# MCU.net
KiCad netlist of a schematic drawn in Altium Designer
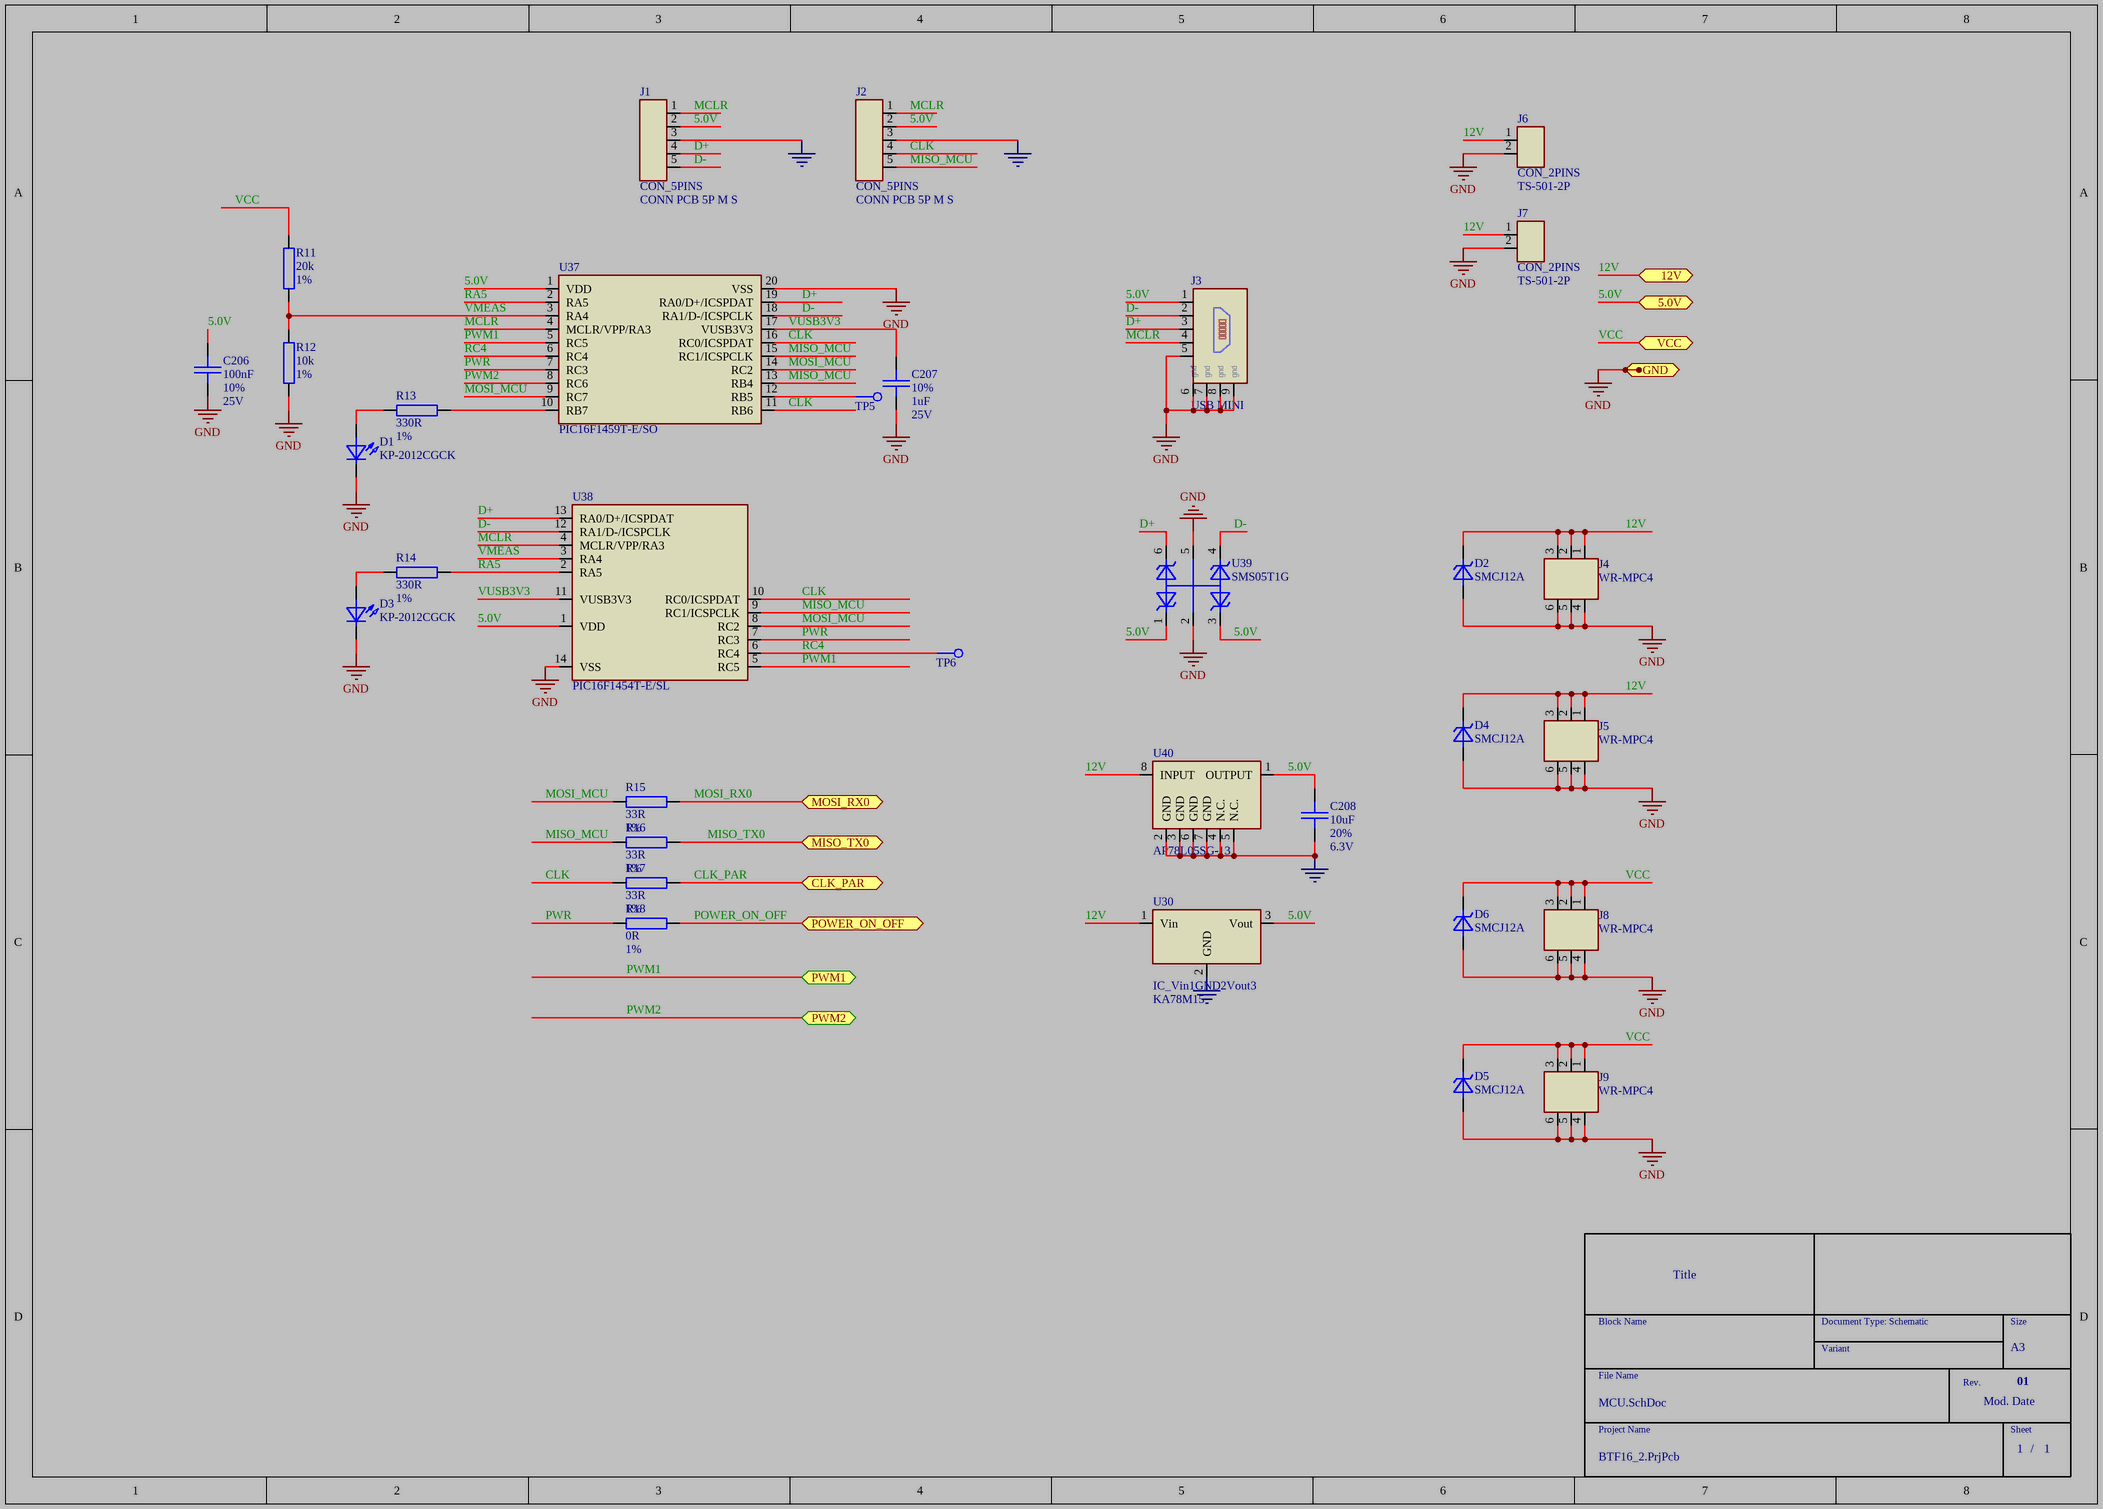
[diagram p0: MCU.SchDoc]

(export (version "E")
  (design (tool "Eeschema 10.0.6"))
  (components
    (comp (ref "C206")
      (value "C")
      (footprint "SMD_0402_CAPC1005X55N")
      (fields
        (field (name "DB_PART_NUMBER") "CAP000047469")
        (field (name "DB_VALUE") "100nF")
        (field (name "DB_TOLERANCE") "10%")
        (field (name "DB_VOLTAGE") "25V")
        (field (name "DB_MANUFACTURER_PART") "SAMSUNG    CL05A104KA5NNNC")
        (field (name "DB_APPROVED_BY") "VSN")
      )
      (libsource (lib "Database_Libs1") (part "C"))
    )
    (comp (ref "C207")
      (value "C")
      (footprint "SMD_0603_CAPC1608X80N")
      (fields
        (field (name "DB_MANUFACTURER_PART") "TDK      CGA3E1X7R1E105KT")
        (field (name "DB_PART_NUMBER") "CAP000047176")
        (field (name "DB_TOLERANCE") "10%")
        (field (name "DB_VALUE") "1uF")
        (field (name "DB_VOLTAGE") "25V")
        (field (name "DB_APPROVED_BY") "VSN")
      )
      (libsource (lib "Database_Libs1") (part "C"))
    )
    (comp (ref "C208")
      (value "C")
      (footprint "SMD_0603_CAPC1608X95N")
      (fields
        (field (name "DB_PART_NUMBER") "CAP000043646")
        (field (name "DB_VALUE") "10uF")
        (field (name "DB_TOLERANCE") "20%")
        (field (name "DB_VOLTAGE") "6.3V")
        (field (name "DB_MANUFACTURER_PART") "KEMET    C0603C106M9PAC")
      )
      (libsource (lib "Database_Libs1") (part "C"))
    )
    (comp (ref "D1")
      (value "LED")
      (footprint "SMD_LED2012X100N")
      (fields
        (field (name "DB_PART_NUMBER") "OPT000000096")
        (field (name "DB_VALUE") "KP-2012CGCK")
        (field (name "DB_MANUFACTURER_PART") "KINGBRIGHT       KP-2012CGCK")
        (field (name "DB_APPROVED_BY") "VSN")
      )
      (libsource (lib "Database_Libs1") (part "LED"))
    )
    (comp (ref "D2")
      (value "D_TVS_UNI")
      (footprint "SMD_DO214AC_SMC")
      (fields
        (field (name "DB_PART_NUMBER") "DDE000001725")
        (field (name "DB_VALUE") "SMCJ12A")
        (field (name "DB_MANUFACTURER_PART") "Diodes        SMCJ12A")
      )
      (libsource (lib "Database_Libs1") (part "D_TVS_UNI"))
    )
    (comp (ref "D3")
      (value "LED")
      (footprint "SMD_LED2012X100N")
      (fields
        (field (name "DB_PART_NUMBER") "OPT000000096")
        (field (name "DB_VALUE") "KP-2012CGCK")
        (field (name "DB_MANUFACTURER_PART") "KINGBRIGHT       KP-2012CGCK")
        (field (name "DB_APPROVED_BY") "VSN")
      )
      (libsource (lib "Database_Libs1") (part "LED"))
    )
    (comp (ref "D4")
      (value "D_TVS_UNI")
      (footprint "SMD_DO214AC_SMC")
      (fields
        (field (name "DB_PART_NUMBER") "DDE000001725")
        (field (name "DB_VALUE") "SMCJ12A")
        (field (name "DB_MANUFACTURER_PART") "Diodes        SMCJ12A")
      )
      (libsource (lib "Database_Libs1") (part "D_TVS_UNI"))
    )
    (comp (ref "D5")
      (value "D_TVS_UNI")
      (footprint "SMD_DO214AC_SMC")
      (fields
        (field (name "DB_PART_NUMBER") "DDE000001725")
        (field (name "DB_VALUE") "SMCJ12A")
        (field (name "DB_MANUFACTURER_PART") "Diodes        SMCJ12A")
      )
      (libsource (lib "Database_Libs1") (part "D_TVS_UNI"))
    )
    (comp (ref "D6")
      (value "D_TVS_UNI")
      (footprint "SMD_DO214AC_SMC")
      (fields
        (field (name "DB_PART_NUMBER") "DDE000001725")
        (field (name "DB_VALUE") "SMCJ12A")
        (field (name "DB_MANUFACTURER_PART") "Diodes        SMCJ12A")
      )
      (libsource (lib "Database_Libs1") (part "D_TVS_UNI"))
    )
    (comp (ref "J1")
      (value "CON_5PINS")
      (footprint "PTH_HDRV05W64P254_1X05")
      (fields
        (field (name "DB_PART_NUMBER") "CON000000006")
        (field (name "DB_VALUE") "CONN PCB 5P M S")
        (field (name "DB_MANUFACTURER_PART") "W+P        143-12-005-00")
        (field (name "DB_APPROVED_BY") "VSN")
      )
      (libsource (lib "Database_Libs1") (part "CON_5PINS"))
    )
    (comp (ref "J2")
      (value "CON_5PINS")
      (footprint "PTH_HDRV05W64P254_1X05")
      (fields
        (field (name "DB_PART_NUMBER") "CON000000006")
        (field (name "DB_VALUE") "CONN PCB 5P M S")
        (field (name "DB_MANUFACTURER_PART") "W+P        143-12-005-00")
        (field (name "DB_APPROVED_BY") "VSN")
      )
      (libsource (lib "Database_Libs1") (part "CON_5PINS"))
    )
    (comp (ref "J3")
      (value "CON_USB_MINI_1")
      (footprint "SMD_CON-CVILUX-CU04-SCM15B0")
      (fields
        (field (name "DB_PART_NUMBER") "CON000000048")
        (field (name "DB_VALUE") "USB MINI")
        (field (name "DB_MANUFACTURER_PART") "CVILUX       CU04-SCM15B0-R0-LF")
        (field (name "DB_APPROVED_BY") "VSN")
      )
      (libsource (lib "Database_Libs1") (part "CON_USB_MINI_1"))
    )
    (comp (ref "J4")
      (value "CON_2ROWS_6PINS_1")
      (footprint "PTH_CON_WR-MRC4-6P_S")
      (fields
        (field (name "DB_PART_NUMBER") "CON000000279")
        (field (name "DB_VALUE") "WR-MPC4")
        (field (name "DB_MANUFACTURER_PART") "WE        	649 006 211 22")
        (field (name "DB_APPROVED_BY") "VSN")
      )
      (libsource (lib "Database_Libs1") (part "CON_2ROWS_6PINS_1"))
    )
    (comp (ref "J5")
      (value "CON_2ROWS_6PINS_1")
      (footprint "PTH_CON_WR-MRC4-6P_S")
      (fields
        (field (name "DB_PART_NUMBER") "CON000000279")
        (field (name "DB_VALUE") "WR-MPC4")
        (field (name "DB_MANUFACTURER_PART") "WE        	649 006 211 22")
        (field (name "DB_APPROVED_BY") "VSN")
      )
      (libsource (lib "Database_Libs1") (part "CON_2ROWS_6PINS_1"))
    )
    (comp (ref "J6")
      (value "CON_2PINS")
      (footprint "PTH_HDRV02W11060P500_1X02")
      (fields
        (field (name "DB_PART_NUMBER") "CON000000055")
        (field (name "DB_VALUE") "TS-501-2P")
        (field (name "DB_MANUFACTURER_PART") "HOW DER      TS-501-2P")
        (field (name "DB_APPROVED_BY") "VSN")
      )
      (libsource (lib "Database_Libs1") (part "CON_2PINS"))
    )
    (comp (ref "J7")
      (value "CON_2PINS")
      (footprint "PTH_HDRV02W11060P500_1X02")
      (fields
        (field (name "DB_PART_NUMBER") "CON000000055")
        (field (name "DB_VALUE") "TS-501-2P")
        (field (name "DB_MANUFACTURER_PART") "HOW DER      TS-501-2P")
        (field (name "DB_APPROVED_BY") "VSN")
      )
      (libsource (lib "Database_Libs1") (part "CON_2PINS"))
    )
    (comp (ref "J8")
      (value "CON_2ROWS_6PINS_1")
      (footprint "PTH_CON_WR-MRC4-6P_S")
      (fields
        (field (name "DB_PART_NUMBER") "CON000000279")
        (field (name "DB_VALUE") "WR-MPC4")
        (field (name "DB_MANUFACTURER_PART") "WE        	649 006 211 22")
        (field (name "DB_APPROVED_BY") "VSN")
      )
      (libsource (lib "Database_Libs1") (part "CON_2ROWS_6PINS_1"))
    )
    (comp (ref "J9")
      (value "CON_2ROWS_6PINS_1")
      (footprint "PTH_CON_WR-MRC4-6P_S")
      (fields
        (field (name "DB_PART_NUMBER") "CON000000279")
        (field (name "DB_VALUE") "WR-MPC4")
        (field (name "DB_MANUFACTURER_PART") "WE        	649 006 211 22")
        (field (name "DB_APPROVED_BY") "VSN")
      )
      (libsource (lib "Database_Libs1") (part "CON_2ROWS_6PINS_1"))
    )
    (comp (ref "R11")
      (value "R")
      (footprint "SMD_0603_RESC1608X55N")
      (fields
        (field (name "DB_PART_NUMBER") "RES000006283")
        (field (name "DB_VALUE") "20k")
        (field (name "DB_TOLERANCE") "1%")
        (field (name "DB_MANUFACTURER_PART") "YAGEO    RC0603FR-0720K")
      )
      (libsource (lib "Database_Libs1") (part "R"))
    )
    (comp (ref "R12")
      (value "R")
      (footprint "SMD_0402_RESC1005X37N")
      (fields
        (field (name "DB_PART_NUMBER") "RES000008887")
        (field (name "DB_VALUE") "10k")
        (field (name "DB_TOLERANCE") "1%")
        (field (name "DB_MANUFACTURER_PART") "VISHAY    CRCW040210K0FKED")
        (field (name "DB_APPROVED_BY") "VSN")
      )
      (libsource (lib "Database_Libs1") (part "R"))
    )
    (comp (ref "R13")
      (value "R")
      (footprint "SMD_0603_RESC1608X55N")
      (fields
        (field (name "DB_PART_NUMBER") "RES000006240")
        (field (name "DB_VALUE") "330R")
        (field (name "DB_TOLERANCE") "1%")
        (field (name "DB_MANUFACTURER_PART") "YAGEO    RC0603FR-07330R")
      )
      (libsource (lib "Database_Libs1") (part "R"))
    )
    (comp (ref "R14")
      (value "R")
      (footprint "SMD_0603_RESC1608X55N")
      (fields
        (field (name "DB_PART_NUMBER") "RES000006240")
        (field (name "DB_VALUE") "330R")
        (field (name "DB_TOLERANCE") "1%")
        (field (name "DB_MANUFACTURER_PART") "YAGEO    RC0603FR-07330R")
      )
      (libsource (lib "Database_Libs1") (part "R"))
    )
    (comp (ref "R15")
      (value "R")
      (footprint "SMD_0402_RESC1005X37N")
      (fields
        (field (name "DB_PART_NUMBER") "RES000005869")
        (field (name "DB_VALUE") "33R")
        (field (name "DB_TOLERANCE") "1%")
        (field (name "DB_MANUFACTURER_PART") "YAGEO    RC0402FR-0733R")
      )
      (libsource (lib "Database_Libs1") (part "R"))
    )
    (comp (ref "R16")
      (value "R")
      (footprint "SMD_0402_RESC1005X37N")
      (fields
        (field (name "DB_PART_NUMBER") "RES000005869")
        (field (name "DB_VALUE") "33R")
        (field (name "DB_TOLERANCE") "1%")
        (field (name "DB_MANUFACTURER_PART") "YAGEO    RC0402FR-0733R")
      )
      (libsource (lib "Database_Libs1") (part "R"))
    )
    (comp (ref "R17")
      (value "R")
      (footprint "SMD_0402_RESC1005X37N")
      (fields
        (field (name "DB_PART_NUMBER") "RES000005869")
        (field (name "DB_VALUE") "33R")
        (field (name "DB_TOLERANCE") "1%")
        (field (name "DB_MANUFACTURER_PART") "YAGEO    RC0402FR-0733R")
      )
      (libsource (lib "Database_Libs1") (part "R"))
    )
    (comp (ref "R18")
      (value "R")
      (footprint "SMD_0603_RESC1608X55N")
      (fields
        (field (name "DB_PART_NUMBER") "RES000008926")
        (field (name "DB_VALUE") "0R")
        (field (name "DB_TOLERANCE") "1%")
        (field (name "DB_MANUFACTURER_PART") "YAGEO    AC0603FR-070RL")
        (field (name "DB_APPROVED_BY") "VSN")
      )
      (libsource (lib "Database_Libs1") (part "R"))
    )
    (comp (ref "TP5")
      (value "TEST_POINT_1")
      (footprint "SMD_TP_100-254")
      (fields (field (name "DB_PART_NUMBER") "TPO000000001"))
      (libsource (lib "Database_Libs1") (part "TEST_POINT_1"))
    )
    (comp (ref "TP6")
      (value "TEST_POINT_1")
      (footprint "SMD_TP_100-254")
      (fields (field (name "DB_PART_NUMBER") "TPO000000001"))
      (libsource (lib "Database_Libs1") (part "TEST_POINT_1"))
    )
    (comp (ref "U30")
      (value "IC_Vin1GND2Vout3")
      (footprint "PTH_TO220")
      (fields
        (field (name "DB_PART_NUMBER") "PSU000000080")
        (field (name "DB_VALUE") "KA78M15")
        (field (name "DB_MANUFACTURER_PART") "FAIRCHILD        KA78M15")
        (field (name "DB_APPROVED_BY") "VSN")
      )
      (libsource (lib "Database_Libs1") (part "IC_Vin1GND2Vout3"))
    )
    (comp (ref "U37")
      (value "IC_PIC16F1459")
      (footprint "SMD_SOIC127P1030X265-20N")
      (fields
        (field (name "DB_PART_NUMBER") "MCU000000108")
        (field (name "DB_VALUE") "PIC16F1459T-E/SO")
        (field (name "DB_MANUFACTURER_PART") "MICROCHIP        PIC16F1459T-E/SO")
        (field (name "DB_APPROVED_BY") "VSN")
      )
      (libsource (lib "Database_Libs1") (part "IC_PIC16F1459"))
    )
    (comp (ref "U38")
      (value "IC_PIC16F1454TESL-SO14")
      (footprint "SMD_SOIC127P600X175-14N")
      (fields
        (field (name "DB_PART_NUMBER") "MCU000000093")
        (field (name "DB_VALUE") "PIC16F1454T-E/SL")
        (field (name "DB_MANUFACTURER_PART") "MICROCHIP       PIC16F1454T-E/SL")
        (field (name "DB_APPROVED_BY") "VSN")
      )
      (libsource (lib "Database_Libs1") (part "IC_PIC16F1454TESL-SO14"))
    )
    (comp (ref "U39")
      (value "D_TVS_QUAD_C1A2C3C4A5C6")
      (footprint "SMD_SOT457_SOT95P275X110-6N")
      (fields
        (field (name "DB_PART_NUMBER") "DDE000002846")
        (field (name "DB_VALUE") "SMS05T1G")
        (field (name "DB_MANUFACTURER_PART") "ON SEMICONDUCTOR        SMS05T1G")
        (field (name "DB_APPROVED_BY") "VSN")
      )
      (libsource (lib "Database_Libs1") (part "D_TVS_QUAD_C1A2C3C4A5C6"))
    )
    (comp (ref "U40")
      (value "IC_LM2931AD-5.0R2G_SO-8")
      (footprint "SMD_SOIC127P600X175-8N")
      (fields
        (field (name "DB_PART_NUMBER") "PSU000000125")
        (field (name "DB_VALUE") "AP78L05SG-13")
        (field (name "DB_MANUFACTURER_PART") "DIODES        AP78L05SG-13")
        (field (name "DB_APPROVED_BY") "VSN")
      )
      (libsource (lib "Database_Libs1") (part "IC_LM2931AD-5.0R2G_SO-8"))
    )
  )
  (nets
    (net (code "1") (name "/5.0V") (class "Default")
      (node (ref "C206") (pin "1") (pinfunction "1_1") (pintype "passive"))
      (node (ref "C208") (pin "1") (pinfunction "1_1") (pintype "passive"))
      (node (ref "J1") (pin "2") (pinfunction "2_2") (pintype "passive"))
      (node (ref "J2") (pin "2") (pinfunction "2_2") (pintype "passive"))
      (node (ref "J3") (pin "1") (pinfunction "1_1") (pintype "passive"))
      (node (ref "U30") (pin "3") (pinfunction "Vout_3") (pintype "passive"))
      (node (ref "U37") (pin "1") (pinfunction "VDD_1") (pintype "passive"))
      (node (ref "U38") (pin "1") (pinfunction "VDD_1") (pintype "passive"))
      (node (ref "U39") (pin "1") (pinfunction "1_1") (pintype "passive"))
      (node (ref "U39") (pin "3") (pinfunction "3_3") (pintype "passive"))
      (node (ref "U40") (pin "1") (pinfunction "OUTPUT_1") (pintype "passive"))
    )
    (net (code "2") (name "/12V") (class "Default")
      (node (ref "D2") (pin "1") (pinfunction "C_1") (pintype "passive"))
      (node (ref "D4") (pin "1") (pinfunction "C_1") (pintype "passive"))
      (node (ref "J4") (pin "1") (pinfunction "1_1") (pintype "passive"))
      (node (ref "J4") (pin "2") (pinfunction "2_2") (pintype "passive"))
      (node (ref "J4") (pin "3") (pinfunction "3_3") (pintype "passive"))
      (node (ref "J5") (pin "1") (pinfunction "1_1") (pintype "passive"))
      (node (ref "J5") (pin "2") (pinfunction "2_2") (pintype "passive"))
      (node (ref "J5") (pin "3") (pinfunction "3_3") (pintype "passive"))
      (node (ref "J6") (pin "1") (pinfunction "1_1") (pintype "passive"))
      (node (ref "J7") (pin "1") (pinfunction "1_1") (pintype "passive"))
      (node (ref "U30") (pin "1") (pinfunction "Vin_1") (pintype "passive"))
      (node (ref "U40") (pin "8") (pinfunction "INPUT_8") (pintype "passive"))
    )
    (net (code "3") (name "/CLK") (class "Default")
      (node (ref "J2") (pin "4") (pinfunction "4_4") (pintype "passive"))
      (node (ref "R17") (pin "1") (pinfunction "1_1") (pintype "passive"))
      (node (ref "U37") (pin "11") (pinfunction "RB6_11") (pintype "passive"))
      (node (ref "U37") (pin "16") (pinfunction "RC0/ICSPDAT_16") (pintype "passive"))
      (node (ref "U38") (pin "10") (pinfunction "RC0/ICSPDAT_10") (pintype "passive"))
    )
    (net (code "4") (name "/CLK_PAR") (class "Default")
      (node (ref "R17") (pin "2") (pinfunction "2_2") (pintype "passive"))
    )
    (net (code "5") (name "/D+") (class "Default")
      (node (ref "J1") (pin "4") (pinfunction "4_4") (pintype "passive"))
      (node (ref "J3") (pin "3") (pinfunction "3_3") (pintype "passive"))
      (node (ref "U37") (pin "19") (pinfunction "RA0/D+/ICSPDAT_19") (pintype "passive"))
      (node (ref "U38") (pin "13") (pinfunction "RA0/D+/ICSPDAT_13") (pintype "passive"))
      (node (ref "U39") (pin "6") (pinfunction "6_6") (pintype "passive"))
    )
    (net (code "6") (name "/D-") (class "Default")
      (node (ref "J1") (pin "5") (pinfunction "5_5") (pintype "passive"))
      (node (ref "J3") (pin "2") (pinfunction "2_2") (pintype "passive"))
      (node (ref "U37") (pin "18") (pinfunction "RA1/D-/ICSPCLK_18") (pintype "passive"))
      (node (ref "U38") (pin "12") (pinfunction "RA1/D-/ICSPCLK_12") (pintype "passive"))
      (node (ref "U39") (pin "4") (pinfunction "4_4") (pintype "passive"))
    )
    (net (code "7") (name "/MCLR") (class "Default")
      (node (ref "J1") (pin "1") (pinfunction "1_1") (pintype "passive"))
      (node (ref "J2") (pin "1") (pinfunction "1_1") (pintype "passive"))
      (node (ref "J3") (pin "4") (pinfunction "4_4") (pintype "passive"))
      (node (ref "U37") (pin "4") (pinfunction "MCLR/VPP/RA3_4") (pintype "passive"))
      (node (ref "U38") (pin "4") (pinfunction "MCLR/VPP/RA3_4") (pintype "passive"))
    )
    (net (code "8") (name "/MISO_MCU") (class "Default")
      (node (ref "J2") (pin "5") (pinfunction "5_5") (pintype "passive"))
      (node (ref "R16") (pin "1") (pinfunction "1_1") (pintype "passive"))
      (node (ref "U37") (pin "13") (pinfunction "RB4_13") (pintype "passive"))
      (node (ref "U37") (pin "15") (pinfunction "RC1/ICSPCLK_15") (pintype "passive"))
      (node (ref "U38") (pin "9") (pinfunction "RC1/ICSPCLK_9") (pintype "passive"))
    )
    (net (code "9") (name "/MISO_TX0") (class "Default")
      (node (ref "R16") (pin "2") (pinfunction "2_2") (pintype "passive"))
    )
    (net (code "10") (name "/MOSI_MCU") (class "Default")
      (node (ref "R15") (pin "1") (pinfunction "1_1") (pintype "passive"))
      (node (ref "U37") (pin "14") (pinfunction "RC2_14") (pintype "passive"))
      (node (ref "U37") (pin "9") (pinfunction "RC7_9") (pintype "passive"))
      (node (ref "U38") (pin "8") (pinfunction "RC2_8") (pintype "passive"))
    )
    (net (code "11") (name "/MOSI_RX0") (class "Default")
      (node (ref "R15") (pin "2") (pinfunction "2_2") (pintype "passive"))
    )
    (net (code "12") (name "/POWER_ON_OFF") (class "Default")
      (node (ref "R18") (pin "2") (pinfunction "2_2") (pintype "passive"))
    )
    (net (code "13") (name "/PWM1") (class "Default")
      (node (ref "U37") (pin "5") (pinfunction "RC5_5") (pintype "passive"))
      (node (ref "U38") (pin "5") (pinfunction "RC5_5") (pintype "passive"))
    )
    (net (code "14") (name "/PWM2") (class "Default")
      (node (ref "U37") (pin "8") (pinfunction "RC6_8") (pintype "passive"))
    )
    (net (code "15") (name "/PWR") (class "Default")
      (node (ref "R18") (pin "1") (pinfunction "1_1") (pintype "passive"))
      (node (ref "U37") (pin "7") (pinfunction "RC3_7") (pintype "passive"))
      (node (ref "U38") (pin "7") (pinfunction "RC3_7") (pintype "passive"))
    )
    (net (code "16") (name "/RA5") (class "Default")
      (node (ref "R14") (pin "2") (pinfunction "2_2") (pintype "passive"))
      (node (ref "U37") (pin "2") (pinfunction "RA5_2") (pintype "passive"))
      (node (ref "U38") (pin "2") (pinfunction "RA5_2") (pintype "passive"))
    )
    (net (code "17") (name "/RC4") (class "Default")
      (node (ref "TP6") (pin "1") (pinfunction "1_1") (pintype "passive"))
      (node (ref "U37") (pin "6") (pinfunction "RC4_6") (pintype "passive"))
      (node (ref "U38") (pin "6") (pinfunction "RC4_6") (pintype "passive"))
    )
    (net (code "18") (name "/VCC") (class "Default")
      (node (ref "D5") (pin "1") (pinfunction "C_1") (pintype "passive"))
      (node (ref "D6") (pin "1") (pinfunction "C_1") (pintype "passive"))
      (node (ref "J8") (pin "1") (pinfunction "1_1") (pintype "passive"))
      (node (ref "J8") (pin "2") (pinfunction "2_2") (pintype "passive"))
      (node (ref "J8") (pin "3") (pinfunction "3_3") (pintype "passive"))
      (node (ref "J9") (pin "1") (pinfunction "1_1") (pintype "passive"))
      (node (ref "J9") (pin "2") (pinfunction "2_2") (pintype "passive"))
      (node (ref "J9") (pin "3") (pinfunction "3_3") (pintype "passive"))
      (node (ref "R11") (pin "1") (pinfunction "1_1") (pintype "passive"))
    )
    (net (code "19") (name "/VMEAS") (class "Default")
      (node (ref "R11") (pin "2") (pinfunction "2_2") (pintype "passive"))
      (node (ref "R12") (pin "1") (pinfunction "1_1") (pintype "passive"))
      (node (ref "U37") (pin "3") (pinfunction "RA4_3") (pintype "passive"))
      (node (ref "U38") (pin "3") (pinfunction "RA4_3") (pintype "passive"))
    )
    (net (code "20") (name "/VUSB3V3") (class "Default")
      (node (ref "C207") (pin "1") (pinfunction "1_1") (pintype "passive"))
      (node (ref "U37") (pin "17") (pinfunction "VUSB3V3_17") (pintype "passive"))
      (node (ref "U38") (pin "11") (pinfunction "VUSB3V3_11") (pintype "passive"))
    )
    (net (code "21") (name "GND") (class "Default")
      (node (ref "C206") (pin "2") (pinfunction "2_2") (pintype "passive"))
      (node (ref "C207") (pin "2") (pinfunction "2_2") (pintype "passive"))
      (node (ref "C208") (pin "2") (pinfunction "2_2") (pintype "passive"))
      (node (ref "D1") (pin "1") (pinfunction "C_1") (pintype "passive"))
      (node (ref "D2") (pin "2") (pinfunction "A_2") (pintype "passive"))
      (node (ref "D3") (pin "1") (pinfunction "C_1") (pintype "passive"))
      (node (ref "D4") (pin "2") (pinfunction "A_2") (pintype "passive"))
      (node (ref "D5") (pin "2") (pinfunction "A_2") (pintype "passive"))
      (node (ref "D6") (pin "2") (pinfunction "A_2") (pintype "passive"))
      (node (ref "J1") (pin "3") (pinfunction "3_3") (pintype "passive"))
      (node (ref "J2") (pin "3") (pinfunction "3_3") (pintype "passive"))
      (node (ref "J3") (pin "5") (pinfunction "5_5") (pintype "passive"))
      (node (ref "J3") (pin "6") (pinfunction "6_6") (pintype "passive"))
      (node (ref "J3") (pin "7") (pinfunction "7_7") (pintype "passive"))
      (node (ref "J3") (pin "8") (pinfunction "8_8") (pintype "passive"))
      (node (ref "J3") (pin "9") (pinfunction "9_9") (pintype "passive"))
      (node (ref "J4") (pin "4") (pinfunction "4_4") (pintype "passive"))
      (node (ref "J4") (pin "5") (pinfunction "5_5") (pintype "passive"))
      (node (ref "J4") (pin "6") (pinfunction "6_6") (pintype "passive"))
      (node (ref "J5") (pin "4") (pinfunction "4_4") (pintype "passive"))
      (node (ref "J5") (pin "5") (pinfunction "5_5") (pintype "passive"))
      (node (ref "J5") (pin "6") (pinfunction "6_6") (pintype "passive"))
      (node (ref "J6") (pin "2") (pinfunction "2_2") (pintype "passive"))
      (node (ref "J7") (pin "2") (pinfunction "2_2") (pintype "passive"))
      (node (ref "J8") (pin "4") (pinfunction "4_4") (pintype "passive"))
      (node (ref "J8") (pin "5") (pinfunction "5_5") (pintype "passive"))
      (node (ref "J8") (pin "6") (pinfunction "6_6") (pintype "passive"))
      (node (ref "J9") (pin "4") (pinfunction "4_4") (pintype "passive"))
      (node (ref "J9") (pin "5") (pinfunction "5_5") (pintype "passive"))
      (node (ref "J9") (pin "6") (pinfunction "6_6") (pintype "passive"))
      (node (ref "R12") (pin "2") (pinfunction "2_2") (pintype "passive"))
      (node (ref "U30") (pin "2") (pinfunction "GND_2") (pintype "passive"))
      (node (ref "U37") (pin "20") (pinfunction "VSS_20") (pintype "passive"))
      (node (ref "U38") (pin "14") (pinfunction "VSS_14") (pintype "passive"))
      (node (ref "U39") (pin "2") (pinfunction "2_2") (pintype "passive"))
      (node (ref "U39") (pin "5") (pinfunction "5_5") (pintype "passive"))
      (node (ref "U40") (pin "2") (pinfunction "GND_2") (pintype "passive"))
      (node (ref "U40") (pin "3") (pinfunction "GND_3") (pintype "passive"))
      (node (ref "U40") (pin "4") (pinfunction "N.C._4") (pintype "passive"))
      (node (ref "U40") (pin "5") (pinfunction "N.C._5") (pintype "passive"))
      (node (ref "U40") (pin "6") (pinfunction "GND_6") (pintype "passive"))
      (node (ref "U40") (pin "7") (pinfunction "GND_7") (pintype "passive"))
    )
    (net (code "22") (name "Net-(D1-A)") (class "Default")
      (node (ref "D1") (pin "2") (pinfunction "A_2") (pintype "passive"))
      (node (ref "R13") (pin "1") (pinfunction "1_1") (pintype "passive"))
    )
    (net (code "23") (name "Net-(D3-A)") (class "Default")
      (node (ref "D3") (pin "2") (pinfunction "A_2") (pintype "passive"))
      (node (ref "R14") (pin "1") (pinfunction "1_1") (pintype "passive"))
    )
    (net (code "24") (name "Net-(U37-RB5)") (class "Default")
      (node (ref "TP5") (pin "1") (pinfunction "1_1") (pintype "passive"))
      (node (ref "U37") (pin "12") (pinfunction "RB5_12") (pintype "passive"))
    )
    (net (code "25") (name "Net-(U37-RB7)") (class "Default")
      (node (ref "R13") (pin "2") (pinfunction "2_2") (pintype "passive"))
      (node (ref "U37") (pin "10") (pinfunction "RB7_10") (pintype "passive"))
    )
  )
)
